# SP1.net
KiCad netlist of a schematic drawn in EAGLE
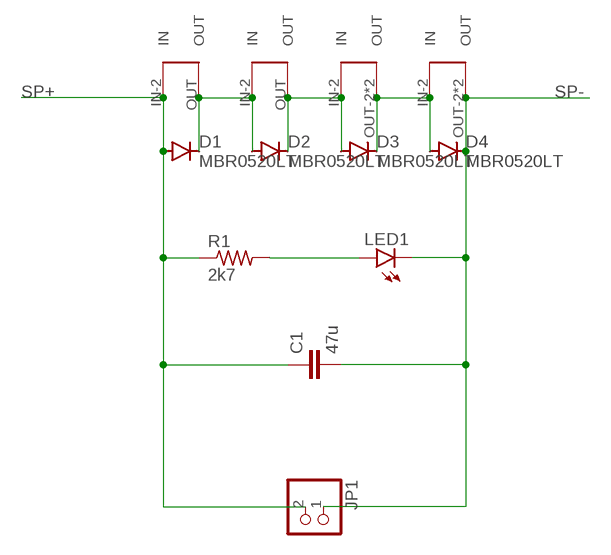
[diagram p0: schematic, sheet 1]

(export (version "E")
  (design (tool "Eeschema 10.0.6"))
  (components
    (comp (ref "C1")
      (value "47u")
      (footprint "eagle-import:C1210")
      (libsource (lib "eagle-import") (part "C-EUC1210"))
    )
    (comp (ref "D1")
      (value "MBR0520LT")
      (footprint "eagle-import:SOD123")
      (libsource (lib "eagle-import") (part "MBR0520LT"))
    )
    (comp (ref "D2")
      (value "MBR0520LT")
      (footprint "eagle-import:SOD123")
      (libsource (lib "eagle-import") (part "MBR0520LT"))
    )
    (comp (ref "D3")
      (value "MBR0520LT")
      (footprint "eagle-import:SOD123")
      (libsource (lib "eagle-import") (part "MBR0520LT"))
    )
    (comp (ref "D4")
      (value "MBR0520LT")
      (footprint "eagle-import:SOD123")
      (libsource (lib "eagle-import") (part "MBR0520LT"))
    )
    (comp (ref "JP1")
      (value "PINHD-1X2")
      (footprint "eagle-import:1X02")
      (libsource (lib "eagle-import") (part "PINHD-1X2"))
    )
    (comp (ref "LED1")
      (value "LEDCHIP-LED0603")
      (footprint "eagle-import:CHIP-LED0603")
      (libsource (lib "eagle-import") (part "LEDCHIP-LED0603"))
    )
    (comp (ref "R1")
      (value "2k7")
      (footprint "eagle-import:R0603")
      (libsource (lib "eagle-import") (part "R-US_R0603"))
    )
    (comp (ref "U$1")
      (value "SOLAR-2_1")
      (footprint "eagle-import:SOLAR_1-2")
      (libsource (lib "eagle-import") (part "SOLAR-2_1"))
    )
    (comp (ref "U$2")
      (value "SOLAR-2_1")
      (footprint "eagle-import:SOLAR_1-2")
      (libsource (lib "eagle-import") (part "SOLAR-2_1"))
    )
    (comp (ref "U$3")
      (value "SOLAR-2_0")
      (footprint "eagle-import:SOLAR_0-2")
      (libsource (lib "eagle-import") (part "SOLAR-2_0"))
    )
    (comp (ref "U$4")
      (value "SOLAR-2_0")
      (footprint "eagle-import:SOLAR_0-2")
      (libsource (lib "eagle-import") (part "SOLAR-2_0"))
    )
  )
  (nets
    (net (code "1") (name "/SP+") (class "Default")
      (node (ref "C1") (pin "1") (pinfunction "1_1") (pintype "passive"))
      (node (ref "D1") (pin "A") (pinfunction "A_A") (pintype "passive"))
      (node (ref "JP1") (pin "2") (pinfunction "2_2") (pintype "passive"))
      (node (ref "R1") (pin "1") (pinfunction "1_1") (pintype "passive"))
      (node (ref "U$1") (pin "IN-2") (pinfunction "IN_IN-2") (pintype "bidirectional"))
    )
    (net (code "2") (name "/SP-") (class "Default")
      (node (ref "C1") (pin "2") (pinfunction "2_2") (pintype "passive"))
      (node (ref "D4") (pin "C") (pinfunction "C_C") (pintype "passive"))
      (node (ref "JP1") (pin "1") (pinfunction "1_1") (pintype "passive"))
      (node (ref "LED1") (pin "C") (pinfunction "C_C") (pintype "passive"))
      (node (ref "U$4") (pin "OUT-2") (pinfunction "OUT_OUT-2") (pintype "bidirectional"))
      (node (ref "U$4") (pin "OUT-21") (pinfunction "OUT_OUT-21") (pintype "bidirectional"))
    )
    (net (code "3") (name "Net-(LED1-PadA)") (class "Default")
      (node (ref "LED1") (pin "A") (pinfunction "A_A") (pintype "passive"))
      (node (ref "R1") (pin "2") (pinfunction "2_2") (pintype "passive"))
    )
    (net (code "4") (name "Net-(U$2-IN)") (class "Default")
      (node (ref "D1") (pin "C") (pinfunction "C_C") (pintype "passive"))
      (node (ref "D2") (pin "A") (pinfunction "A_A") (pintype "passive"))
      (node (ref "U$1") (pin "OUT") (pinfunction "OUT_OUT") (pintype "bidirectional"))
      (node (ref "U$2") (pin "IN-2") (pinfunction "IN_IN-2") (pintype "bidirectional"))
    )
    (net (code "5") (name "Net-(U$3-IN)") (class "Default")
      (node (ref "D2") (pin "C") (pinfunction "C_C") (pintype "passive"))
      (node (ref "D3") (pin "A") (pinfunction "A_A") (pintype "passive"))
      (node (ref "U$2") (pin "OUT") (pinfunction "OUT_OUT") (pintype "bidirectional"))
      (node (ref "U$3") (pin "IN-2") (pinfunction "IN_IN-2") (pintype "bidirectional"))
    )
    (net (code "6") (name "Net-(U$4-IN)") (class "Default")
      (node (ref "D3") (pin "C") (pinfunction "C_C") (pintype "passive"))
      (node (ref "D4") (pin "A") (pinfunction "A_A") (pintype "passive"))
      (node (ref "U$3") (pin "OUT-2") (pinfunction "OUT_OUT-2") (pintype "bidirectional"))
      (node (ref "U$3") (pin "OUT-21") (pinfunction "OUT_OUT-21") (pintype "bidirectional"))
      (node (ref "U$4") (pin "IN-2") (pinfunction "IN_IN-2") (pintype "bidirectional"))
    )
  )
)
